# pcu.net
KiCad netlist of a schematic drawn in EAGLE
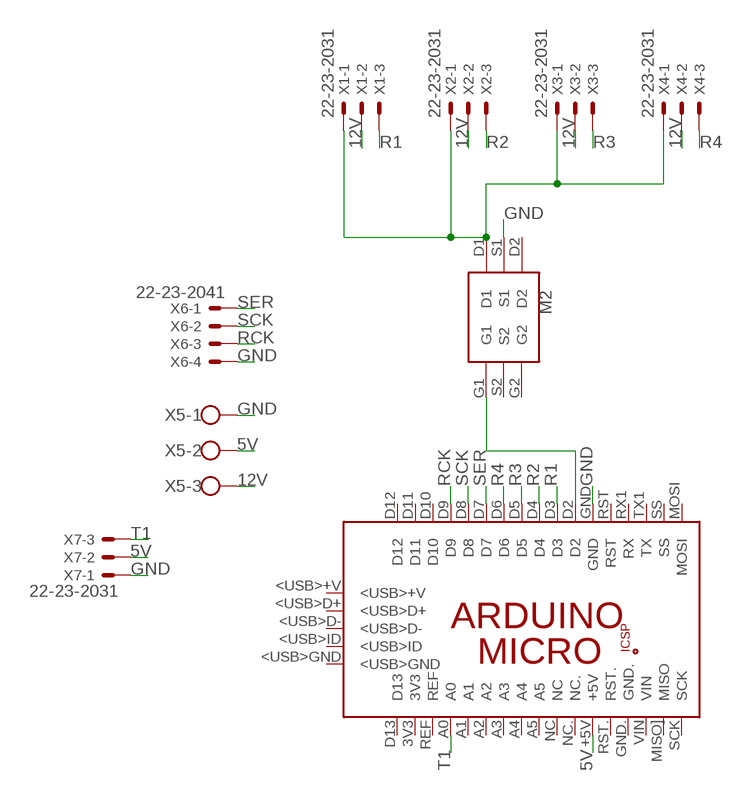
[diagram p0: schematic, sheet 1]

(export (version "E")
  (design (tool "Eeschema 10.0.6"))
  (components
    (comp (ref "M2")
      (value "FDC6305N")
      (footprint "eagle-import:FDC6305")
      (libsource (lib "eagle-import") (part "FDC6305N"))
    )
    (comp (ref "PCB1")
      (value "ARDUINO_MICRO")
      (footprint "eagle-import:ARDUINO_MICRO")
      (libsource (lib "eagle-import") (part "ARDUINO_MICRO"))
    )
    (comp (ref "X1")
      (value "22-23-2031")
      (footprint "eagle-import:22-23-2031")
      (fields (field (name "MF") "MOLEX"))
      (libsource (lib "eagle-import") (part "22-23-2031"))
    )
    (comp (ref "X2")
      (value "22-23-2031")
      (footprint "eagle-import:22-23-2031")
      (fields (field (name "MF") "MOLEX"))
      (libsource (lib "eagle-import") (part "22-23-2031"))
    )
    (comp (ref "X3")
      (value "22-23-2031")
      (footprint "eagle-import:22-23-2031")
      (fields (field (name "MF") "MOLEX"))
      (libsource (lib "eagle-import") (part "22-23-2031"))
    )
    (comp (ref "X4")
      (value "22-23-2031")
      (footprint "eagle-import:22-23-2031")
      (fields (field (name "MF") "MOLEX"))
      (libsource (lib "eagle-import") (part "22-23-2031"))
    )
    (comp (ref "X5")
      (value "W237-103")
      (footprint "eagle-import:W237-103")
      (fields (field (name "MPN") "237-103"))
      (libsource (lib "eagle-import") (part "W237-103"))
    )
    (comp (ref "X6")
      (value "22-23-2041")
      (footprint "eagle-import:22-23-2041")
      (fields (field (name "MF") "MOLEX"))
      (libsource (lib "eagle-import") (part "22-23-2041"))
    )
    (comp (ref "X7")
      (value "22-23-2031")
      (footprint "eagle-import:22-23-2031")
      (fields (field (name "MF") "MOLEX"))
      (libsource (lib "eagle-import") (part "22-23-2031"))
    )
  )
  (nets
    (net (code "1") (name "/5V") (class "Default")
      (node (ref "PCB1") (pin "+5V") (pinfunction "+5V_+5V") (pintype "bidirectional"))
      (node (ref "X5") (pin "2") (pinfunction "KL_2") (pintype "passive"))
      (node (ref "X7") (pin "2") (pinfunction "S_2") (pintype "passive"))
    )
    (net (code "2") (name "/12V") (class "Default")
      (node (ref "X1") (pin "2") (pinfunction "S_2") (pintype "passive"))
      (node (ref "X2") (pin "2") (pinfunction "S_2") (pintype "passive"))
      (node (ref "X3") (pin "2") (pinfunction "S_2") (pintype "passive"))
      (node (ref "X4") (pin "2") (pinfunction "S_2") (pintype "passive"))
      (node (ref "X5") (pin "3") (pinfunction "KL_3") (pintype "passive"))
    )
    (net (code "3") (name "/GND") (class "Default")
      (node (ref "M2") (pin "S1") (pinfunction "S1_S1") (pintype "bidirectional"))
      (node (ref "PCB1") (pin "GND") (pinfunction "GND_GND") (pintype "bidirectional"))
      (node (ref "X5") (pin "1") (pinfunction "KL_1") (pintype "passive"))
      (node (ref "X6") (pin "4") (pinfunction "S_4") (pintype "passive"))
      (node (ref "X7") (pin "1") (pinfunction "S_1") (pintype "passive"))
    )
    (net (code "4") (name "/R1") (class "Default")
      (node (ref "PCB1") (pin "D3") (pinfunction "D3_D3") (pintype "bidirectional"))
      (node (ref "X1") (pin "3") (pinfunction "S_3") (pintype "passive"))
    )
    (net (code "5") (name "/R2") (class "Default")
      (node (ref "PCB1") (pin "D4") (pinfunction "D4_D4") (pintype "bidirectional"))
      (node (ref "X2") (pin "3") (pinfunction "S_3") (pintype "passive"))
    )
    (net (code "6") (name "/R3") (class "Default")
      (node (ref "PCB1") (pin "D5") (pinfunction "D5_D5") (pintype "bidirectional"))
      (node (ref "X3") (pin "3") (pinfunction "S_3") (pintype "passive"))
    )
    (net (code "7") (name "/R4") (class "Default")
      (node (ref "PCB1") (pin "D6") (pinfunction "D6_D6") (pintype "bidirectional"))
      (node (ref "X4") (pin "3") (pinfunction "S_3") (pintype "passive"))
    )
    (net (code "8") (name "/RCK") (class "Default")
      (node (ref "PCB1") (pin "D9") (pinfunction "D9_D9") (pintype "bidirectional"))
      (node (ref "X6") (pin "3") (pinfunction "S_3") (pintype "passive"))
    )
    (net (code "9") (name "/SCK") (class "Default")
      (node (ref "PCB1") (pin "D8") (pinfunction "D8_D8") (pintype "bidirectional"))
      (node (ref "X6") (pin "2") (pinfunction "S_2") (pintype "passive"))
    )
    (net (code "10") (name "/SER") (class "Default")
      (node (ref "PCB1") (pin "D7") (pinfunction "D7_D7") (pintype "bidirectional"))
      (node (ref "X6") (pin "1") (pinfunction "S_1") (pintype "passive"))
    )
    (net (code "11") (name "/T1") (class "Default")
      (node (ref "PCB1") (pin "A0") (pinfunction "A0_A0") (pintype "bidirectional"))
      (node (ref "X7") (pin "3") (pinfunction "S_3") (pintype "passive"))
    )
    (net (code "12") (name "Net-(M2-PadG1)") (class "Default")
      (node (ref "M2") (pin "G1") (pinfunction "G1_G1") (pintype "bidirectional"))
      (node (ref "PCB1") (pin "D2") (pinfunction "D2_D2") (pintype "bidirectional"))
    )
    (net (code "13") (name "Net-(X1A-S)") (class "Default")
      (node (ref "M2") (pin "D1") (pinfunction "D1_D1") (pintype "bidirectional"))
      (node (ref "X1") (pin "1") (pinfunction "S_1") (pintype "passive"))
      (node (ref "X2") (pin "1") (pinfunction "S_1") (pintype "passive"))
      (node (ref "X3") (pin "1") (pinfunction "S_1") (pintype "passive"))
      (node (ref "X4") (pin "1") (pinfunction "S_1") (pintype "passive"))
    )
    (net (code "14") (name "unconnected-(M2-PadD2)") (class "Default")
      (node (ref "M2") (pin "D2") (pinfunction "D2_D2") (pintype "bidirectional"))
    )
    (net (code "15") (name "unconnected-(M2-PadG2)") (class "Default")
      (node (ref "M2") (pin "G2") (pinfunction "G2_G2") (pintype "bidirectional"))
    )
    (net (code "16") (name "unconnected-(M2-PadS2)") (class "Default")
      (node (ref "M2") (pin "S2") (pinfunction "S2_S2") (pintype "bidirectional"))
    )
    (net (code "17") (name "unconnected-(PCB1-MISO-PadMISO])") (class "Default")
      (node (ref "PCB1") (pin "MISO]") (pinfunction "MISO_MISO]") (pintype "bidirectional"))
    )
    (net (code "18") (name "unconnected-(PCB1-Pad3V3)") (class "Default")
      (node (ref "PCB1") (pin "3V3") (pinfunction "3V3_3V3") (pintype "bidirectional"))
    )
    (net (code "19") (name "unconnected-(PCB1-Pad5V)") (class "Default")
      (node (ref "PCB1") (pin "5V") (pinfunction "5V_5V") (pintype "bidirectional"))
    )
    (net (code "20") (name "unconnected-(PCB1-Pad<USB>+V)") (class "Default")
      (node (ref "PCB1") (pin "<USB>+V") (pinfunction "<USB>+V_<USB>+V") (pintype "bidirectional"))
    )
    (net (code "21") (name "unconnected-(PCB1-Pad<USB>D+)") (class "Default")
      (node (ref "PCB1") (pin "<USB>D+") (pinfunction "<USB>D+_<USB>D+") (pintype "bidirectional"))
    )
    (net (code "22") (name "unconnected-(PCB1-Pad<USB>D-)") (class "Default")
      (node (ref "PCB1") (pin "<USB>D-") (pinfunction "<USB>D-_<USB>D-") (pintype "bidirectional"))
    )
    (net (code "23") (name "unconnected-(PCB1-Pad<USB>GND)") (class "Default")
      (node (ref "PCB1") (pin "<USB>GND") (pinfunction "<USB>GND_<USB>GND") (pintype "bidirectional"))
    )
    (net (code "24") (name "unconnected-(PCB1-Pad<USB>ID)") (class "Default")
      (node (ref "PCB1") (pin "<USB>ID") (pinfunction "<USB>ID_<USB>ID") (pintype "bidirectional"))
    )
    (net (code "25") (name "unconnected-(PCB1-PadA1)") (class "Default")
      (node (ref "PCB1") (pin "A1") (pinfunction "A1_A1") (pintype "bidirectional"))
    )
    (net (code "26") (name "unconnected-(PCB1-PadA2)") (class "Default")
      (node (ref "PCB1") (pin "A2") (pinfunction "A2_A2") (pintype "bidirectional"))
    )
    (net (code "27") (name "unconnected-(PCB1-PadA3)") (class "Default")
      (node (ref "PCB1") (pin "A3") (pinfunction "A3_A3") (pintype "bidirectional"))
    )
    (net (code "28") (name "unconnected-(PCB1-PadA4)") (class "Default")
      (node (ref "PCB1") (pin "A4") (pinfunction "A4_A4") (pintype "bidirectional"))
    )
    (net (code "29") (name "unconnected-(PCB1-PadA5)") (class "Default")
      (node (ref "PCB1") (pin "A5") (pinfunction "A5_A5") (pintype "bidirectional"))
    )
    (net (code "30") (name "unconnected-(PCB1-PadD10)") (class "Default")
      (node (ref "PCB1") (pin "D10") (pinfunction "D10_D10") (pintype "bidirectional"))
    )
    (net (code "31") (name "unconnected-(PCB1-PadD11)") (class "Default")
      (node (ref "PCB1") (pin "D11") (pinfunction "D11_D11") (pintype "bidirectional"))
    )
    (net (code "32") (name "unconnected-(PCB1-PadD12)") (class "Default")
      (node (ref "PCB1") (pin "D12") (pinfunction "D12_D12") (pintype "bidirectional"))
    )
    (net (code "33") (name "unconnected-(PCB1-PadD13)") (class "Default")
      (node (ref "PCB1") (pin "D13") (pinfunction "D13_D13") (pintype "bidirectional"))
    )
    (net (code "34") (name "unconnected-(PCB1-PadGND.)") (class "Default")
      (node (ref "PCB1") (pin "GND.") (pinfunction "GND._GND.") (pintype "bidirectional"))
    )
    (net (code "35") (name "unconnected-(PCB1-PadGND_)") (class "Default")
      (node (ref "PCB1") (pin "GND_") (pinfunction "GND__GND_") (pintype "bidirectional"))
    )
    (net (code "36") (name "unconnected-(PCB1-PadMISO.)") (class "Default")
      (node (ref "PCB1") (pin "MISO.") (pinfunction "MISO._MISO.") (pintype "bidirectional"))
    )
    (net (code "37") (name "unconnected-(PCB1-PadMOSI)") (class "Default")
      (node (ref "PCB1") (pin "MOSI") (pinfunction "MOSI_MOSI") (pintype "bidirectional"))
    )
    (net (code "38") (name "unconnected-(PCB1-PadMOSI.)") (class "Default")
      (node (ref "PCB1") (pin "MOSI.") (pinfunction "MOSI._MOSI.") (pintype "bidirectional"))
    )
    (net (code "39") (name "unconnected-(PCB1-PadNC)") (class "Default")
      (node (ref "PCB1") (pin "NC") (pinfunction "NC_NC") (pintype "bidirectional"))
    )
    (net (code "40") (name "unconnected-(PCB1-PadNC.)") (class "Default")
      (node (ref "PCB1") (pin "NC.") (pinfunction "NC._NC.") (pintype "bidirectional"))
    )
    (net (code "41") (name "unconnected-(PCB1-PadREF)") (class "Default")
      (node (ref "PCB1") (pin "REF") (pinfunction "REF_REF") (pintype "bidirectional"))
    )
    (net (code "42") (name "unconnected-(PCB1-PadRESET..)") (class "Default")
      (node (ref "PCB1") (pin "RESET..") (pinfunction "RESET.._RESET..") (pintype "bidirectional"))
    )
    (net (code "43") (name "unconnected-(PCB1-PadRST)") (class "Default")
      (node (ref "PCB1") (pin "RST") (pinfunction "RST_RST") (pintype "bidirectional"))
    )
    (net (code "44") (name "unconnected-(PCB1-PadRST.)") (class "Default")
      (node (ref "PCB1") (pin "RST.") (pinfunction "RST._RST.") (pintype "bidirectional"))
    )
    (net (code "45") (name "unconnected-(PCB1-PadSCK)") (class "Default")
      (node (ref "PCB1") (pin "SCK") (pinfunction "SCK_SCK") (pintype "bidirectional"))
    )
    (net (code "46") (name "unconnected-(PCB1-PadSCK.)") (class "Default")
      (node (ref "PCB1") (pin "SCK.") (pinfunction "SCK._SCK.") (pintype "bidirectional"))
    )
    (net (code "47") (name "unconnected-(PCB1-PadSS)") (class "Default")
      (node (ref "PCB1") (pin "SS") (pinfunction "SS_SS") (pintype "bidirectional"))
    )
    (net (code "48") (name "unconnected-(PCB1-PadVIN)") (class "Default")
      (node (ref "PCB1") (pin "VIN") (pinfunction "VIN_VIN") (pintype "bidirectional"))
    )
    (net (code "49") (name "unconnected-(PCB1-RX-PadRX1)") (class "Default")
      (node (ref "PCB1") (pin "RX1") (pinfunction "RX_RX1") (pintype "bidirectional"))
    )
    (net (code "50") (name "unconnected-(PCB1-TX-PadTX1)") (class "Default")
      (node (ref "PCB1") (pin "TX1") (pinfunction "TX_TX1") (pintype "bidirectional"))
    )
  )
)
